# ambihat.net
KiCad netlist of a schematic drawn in EAGLE
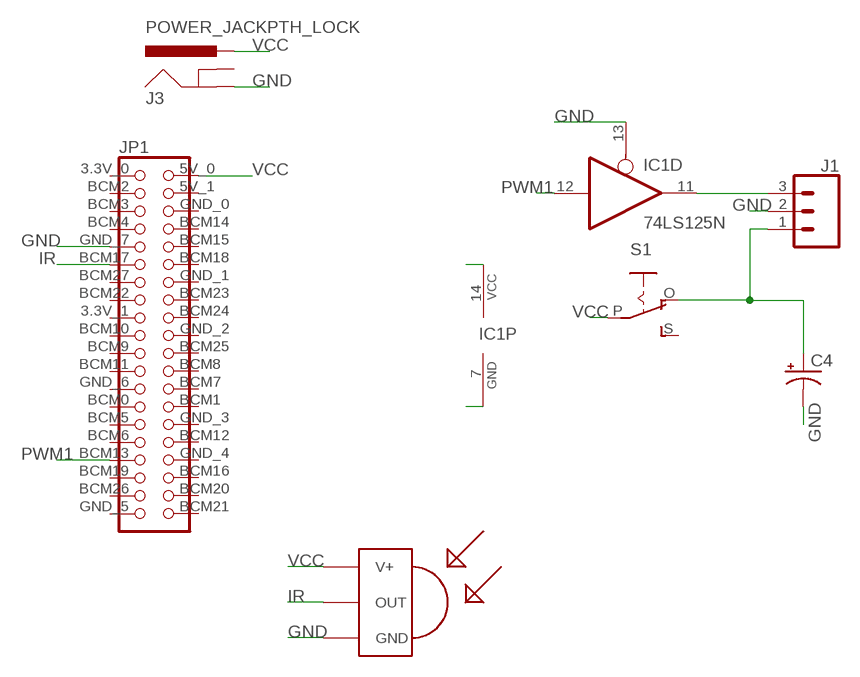
[diagram p0: schematic, sheet 1]

(export (version "E")
  (design (tool "Eeschema 10.0.6"))
  (components
    (comp (ref "C4")
      (value "CPOL-USE5-10.5")
      (footprint "eagle-import:E5-10,5")
      (libsource (lib "eagle-import") (part "CPOL-USE5-10.5"))
    )
    (comp (ref "IC1")
      (value "74LS125N")
      (footprint "eagle-import:DIL14")
      (libsource (lib "eagle-import") (part "74125NLS"))
    )
    (comp (ref "J1")
      (value "CONN_03JST-PTH-VERT")
      (footprint "eagle-import:JST-3-PTH-VERT")
      (libsource (lib "eagle-import") (part "CONN_03JST-PTH-VERT"))
    )
    (comp (ref "J3")
      (value "POWER_JACKPTH_LOCK")
      (footprint "eagle-import:POWER_JACK_PTH_LOCK")
      (libsource (lib "eagle-import") (part "POWER_JACKPTH_LOCK"))
    )
    (comp (ref "JP1")
      (value "RASPBERRY-HEADER")
      (footprint "eagle-import:RASPBERRY-HEADER")
      (libsource (lib "eagle-import") (part "RASPBERRY-HEADER"))
    )
    (comp (ref "S1")
      (value "EG1218S")
      (footprint "eagle-import:EG1218")
      (libsource (lib "eagle-import") (part "EG1218S"))
    )
    (comp (ref "U$1")
      (value "TSOP4838")
      (footprint "eagle-import:TSOP18XX")
      (libsource (lib "eagle-import") (part "TSOP4838"))
    )
  )
  (nets
    (net (code "1") (name "/GND") (class "Default")
      (node (ref "C4") (pin "-") (pinfunction "-_-") (pintype "passive"))
      (node (ref "IC1") (pin "13") (pinfunction "OE_13") (pintype "input"))
      (node (ref "IC1") (pin "7") (pinfunction "GND_7") (pintype "power_in"))
      (node (ref "J1") (pin "2") (pinfunction "2_2") (pintype "passive"))
      (node (ref "J3") (pin "GND") (pinfunction "GND_GND") (pintype "bidirectional"))
      (node (ref "JP1") (pin "GND_7") (pinfunction "9_GND_GND_7") (pintype "passive"))
      (node (ref "U$1") (pin "GND") (pinfunction "GND_GND") (pintype "bidirectional"))
    )
    (net (code "2") (name "/IR") (class "Default")
      (node (ref "JP1") (pin "BCM17") (pinfunction "11_BCM17_BCM17") (pintype "passive"))
      (node (ref "U$1") (pin "OUT") (pinfunction "OUT_OUT") (pintype "bidirectional"))
    )
    (net (code "3") (name "/PWM1") (class "Default")
      (node (ref "IC1") (pin "12") (pinfunction "I_12") (pintype "input"))
      (node (ref "JP1") (pin "BCM13") (pinfunction "33_BCM13_PWM1_BCM13") (pintype "passive"))
    )
    (net (code "4") (name "/VCC") (class "Default")
      (node (ref "IC1") (pin "14") (pinfunction "VCC_14") (pintype "power_in"))
      (node (ref "J3") (pin "PWR") (pinfunction "PWR_PWR") (pintype "bidirectional"))
      (node (ref "JP1") (pin "5V_0") (pinfunction "5V_1_5V_0") (pintype "passive"))
      (node (ref "S1") (pin "P") (pinfunction "P_P") (pintype "passive"))
      (node (ref "U$1") (pin "VCC") (pinfunction "V+_VCC") (pintype "bidirectional"))
    )
    (net (code "5") (name "Net-(C4-Pad+)") (class "Default")
      (node (ref "C4") (pin "+") (pinfunction "+_+") (pintype "passive"))
      (node (ref "J1") (pin "1") (pinfunction "1_1") (pintype "passive"))
      (node (ref "S1") (pin "O") (pinfunction "O_O") (pintype "passive"))
    )
    (net (code "6") (name "Net-(IC1D-O)") (class "Default")
      (node (ref "IC1") (pin "11") (pinfunction "O_11") (pintype "tri_state"))
      (node (ref "J1") (pin "3") (pinfunction "3_3") (pintype "passive"))
    )
    (net (code "7") (name "unconnected-(J3-PadGNDBREAK)") (class "Default")
      (node (ref "J3") (pin "GNDBREAK") (pinfunction "GNDBREAK_GNDBREAK") (pintype "bidirectional"))
    )
    (net (code "8") (name "unconnected-(JP1-1_3V3-Pad3.3V_0)") (class "Default")
      (node (ref "JP1") (pin "3.3V_0") (pinfunction "1_3V3_3.3V_0") (pintype "passive"))
    )
    (net (code "9") (name "unconnected-(JP1-3_BCM2_SDA-PadBCM2)") (class "Default")
      (node (ref "JP1") (pin "BCM2") (pinfunction "3_BCM2_SDA_BCM2") (pintype "passive"))
    )
    (net (code "10") (name "unconnected-(JP1-4_5V5-Pad5V_1)") (class "Default")
      (node (ref "JP1") (pin "5V_1") (pinfunction "4_5V5_5V_1") (pintype "passive"))
    )
    (net (code "11") (name "unconnected-(JP1-5_BCM3_SCL-PadBCM3)") (class "Default")
      (node (ref "JP1") (pin "BCM3") (pinfunction "5_BCM3_SCL_BCM3") (pintype "passive"))
    )
    (net (code "12") (name "unconnected-(JP1-6_GND-PadGND_0)") (class "Default")
      (node (ref "JP1") (pin "GND_0") (pinfunction "6_GND_GND_0") (pintype "passive"))
    )
    (net (code "13") (name "unconnected-(JP1-7_BCM4_GPCLK0-PadBCM4)") (class "Default")
      (node (ref "JP1") (pin "BCM4") (pinfunction "7_BCM4_GPCLK0_BCM4") (pintype "passive"))
    )
    (net (code "14") (name "unconnected-(JP1-8_BCM14_TXD-PadBCM14)") (class "Default")
      (node (ref "JP1") (pin "BCM14") (pinfunction "8_BCM14_TXD_BCM14") (pintype "passive"))
    )
    (net (code "15") (name "unconnected-(JP1-10_BCM15_RXD-PadBCM15)") (class "Default")
      (node (ref "JP1") (pin "BCM15") (pinfunction "10_BCM15_RXD_BCM15") (pintype "passive"))
    )
    (net (code "16") (name "unconnected-(JP1-12_BCM18_PWM0-PadBCM18)") (class "Default")
      (node (ref "JP1") (pin "BCM18") (pinfunction "12_BCM18_PWM0_BCM18") (pintype "passive"))
    )
    (net (code "17") (name "unconnected-(JP1-13_BCM27-PadBCM27)") (class "Default")
      (node (ref "JP1") (pin "BCM27") (pinfunction "13_BCM27_BCM27") (pintype "passive"))
    )
    (net (code "18") (name "unconnected-(JP1-14_GND-PadGND_1)") (class "Default")
      (node (ref "JP1") (pin "GND_1") (pinfunction "14_GND_GND_1") (pintype "passive"))
    )
    (net (code "19") (name "unconnected-(JP1-15_BCM22-PadBCM22)") (class "Default")
      (node (ref "JP1") (pin "BCM22") (pinfunction "15_BCM22_BCM22") (pintype "passive"))
    )
    (net (code "20") (name "unconnected-(JP1-16_BCM23-PadBCM23)") (class "Default")
      (node (ref "JP1") (pin "BCM23") (pinfunction "16_BCM23_BCM23") (pintype "passive"))
    )
    (net (code "21") (name "unconnected-(JP1-17_3V3-Pad3.3V_1)") (class "Default")
      (node (ref "JP1") (pin "3.3V_1") (pinfunction "17_3V3_3.3V_1") (pintype "passive"))
    )
    (net (code "22") (name "unconnected-(JP1-18_BCM24-PadBCM24)") (class "Default")
      (node (ref "JP1") (pin "BCM24") (pinfunction "18_BCM24_BCM24") (pintype "passive"))
    )
    (net (code "23") (name "unconnected-(JP1-19_BCM10_MOSI-PadBCM10)") (class "Default")
      (node (ref "JP1") (pin "BCM10") (pinfunction "19_BCM10_MOSI_BCM10") (pintype "passive"))
    )
    (net (code "24") (name "unconnected-(JP1-20_GND-PadGND_2)") (class "Default")
      (node (ref "JP1") (pin "GND_2") (pinfunction "20_GND_GND_2") (pintype "passive"))
    )
    (net (code "25") (name "unconnected-(JP1-21_BCM9_MISO-PadBCM9)") (class "Default")
      (node (ref "JP1") (pin "BCM9") (pinfunction "21_BCM9_MISO_BCM9") (pintype "passive"))
    )
    (net (code "26") (name "unconnected-(JP1-22_BCM25-PadBCM25)") (class "Default")
      (node (ref "JP1") (pin "BCM25") (pinfunction "22_BCM25_BCM25") (pintype "passive"))
    )
    (net (code "27") (name "unconnected-(JP1-23_BCM11-PadBCM11)") (class "Default")
      (node (ref "JP1") (pin "BCM11") (pinfunction "23_BCM11_BCM11") (pintype "passive"))
    )
    (net (code "28") (name "unconnected-(JP1-24_BCM8_CE0-PadBCM8)") (class "Default")
      (node (ref "JP1") (pin "BCM8") (pinfunction "24_BCM8_CE0_BCM8") (pintype "passive"))
    )
    (net (code "29") (name "unconnected-(JP1-26_BCM7_CE1-PadBCM7)") (class "Default")
      (node (ref "JP1") (pin "BCM7") (pinfunction "26_BCM7_CE1_BCM7") (pintype "passive"))
    )
    (net (code "30") (name "unconnected-(JP1-27_BCM0_ID_SD-PadBCM0)") (class "Default")
      (node (ref "JP1") (pin "BCM0") (pinfunction "27_BCM0_ID_SD_BCM0") (pintype "passive"))
    )
    (net (code "31") (name "unconnected-(JP1-28_BCM1_ID_SC-PadBCM1)") (class "Default")
      (node (ref "JP1") (pin "BCM1") (pinfunction "28_BCM1_ID_SC_BCM1") (pintype "passive"))
    )
    (net (code "32") (name "unconnected-(JP1-29_BCM5-PadBCM5)") (class "Default")
      (node (ref "JP1") (pin "BCM5") (pinfunction "29_BCM5_BCM5") (pintype "passive"))
    )
    (net (code "33") (name "unconnected-(JP1-30_GND-PadGND_3)") (class "Default")
      (node (ref "JP1") (pin "GND_3") (pinfunction "30_GND_GND_3") (pintype "passive"))
    )
    (net (code "34") (name "unconnected-(JP1-31_BCM6-PadBCM6)") (class "Default")
      (node (ref "JP1") (pin "BCM6") (pinfunction "31_BCM6_BCM6") (pintype "passive"))
    )
    (net (code "35") (name "unconnected-(JP1-32_BCM12_PWM0-PadBCM12)") (class "Default")
      (node (ref "JP1") (pin "BCM12") (pinfunction "32_BCM12_PWM0_BCM12") (pintype "passive"))
    )
    (net (code "36") (name "unconnected-(JP1-34_GND-PadGND_4)") (class "Default")
      (node (ref "JP1") (pin "GND_4") (pinfunction "34_GND_GND_4") (pintype "passive"))
    )
    (net (code "37") (name "unconnected-(JP1-35_BCM19_MISO-PadBCM19)") (class "Default")
      (node (ref "JP1") (pin "BCM19") (pinfunction "35_BCM19_MISO_BCM19") (pintype "passive"))
    )
    (net (code "38") (name "unconnected-(JP1-36_BCM16-PadBCM16)") (class "Default")
      (node (ref "JP1") (pin "BCM16") (pinfunction "36_BCM16_BCM16") (pintype "passive"))
    )
    (net (code "39") (name "unconnected-(JP1-37_BCM26-PadBCM26)") (class "Default")
      (node (ref "JP1") (pin "BCM26") (pinfunction "37_BCM26_BCM26") (pintype "passive"))
    )
    (net (code "40") (name "unconnected-(JP1-38_BCM20_MOSI-PadBCM20)") (class "Default")
      (node (ref "JP1") (pin "BCM20") (pinfunction "38_BCM20_MOSI_BCM20") (pintype "passive"))
    )
    (net (code "41") (name "unconnected-(JP1-39_GND-PadGND_5)") (class "Default")
      (node (ref "JP1") (pin "GND_5") (pinfunction "39_GND_GND_5") (pintype "passive"))
    )
    (net (code "42") (name "unconnected-(JP1-40_BCM21_SCLK-PadBCM21)") (class "Default")
      (node (ref "JP1") (pin "BCM21") (pinfunction "40_BCM21_SCLK_BCM21") (pintype "passive"))
    )
    (net (code "43") (name "unconnected-(JP1-GND-PadGND_6)") (class "Default")
      (node (ref "JP1") (pin "GND_6") (pinfunction "GND_GND_6") (pintype "passive"))
    )
    (net (code "44") (name "unconnected-(S1-PadS)") (class "Default")
      (node (ref "S1") (pin "S") (pinfunction "S_S") (pintype "passive"))
    )
  )
)
